# MINI_SAM_D51_007.net
KiCad netlist of a schematic drawn in EAGLE
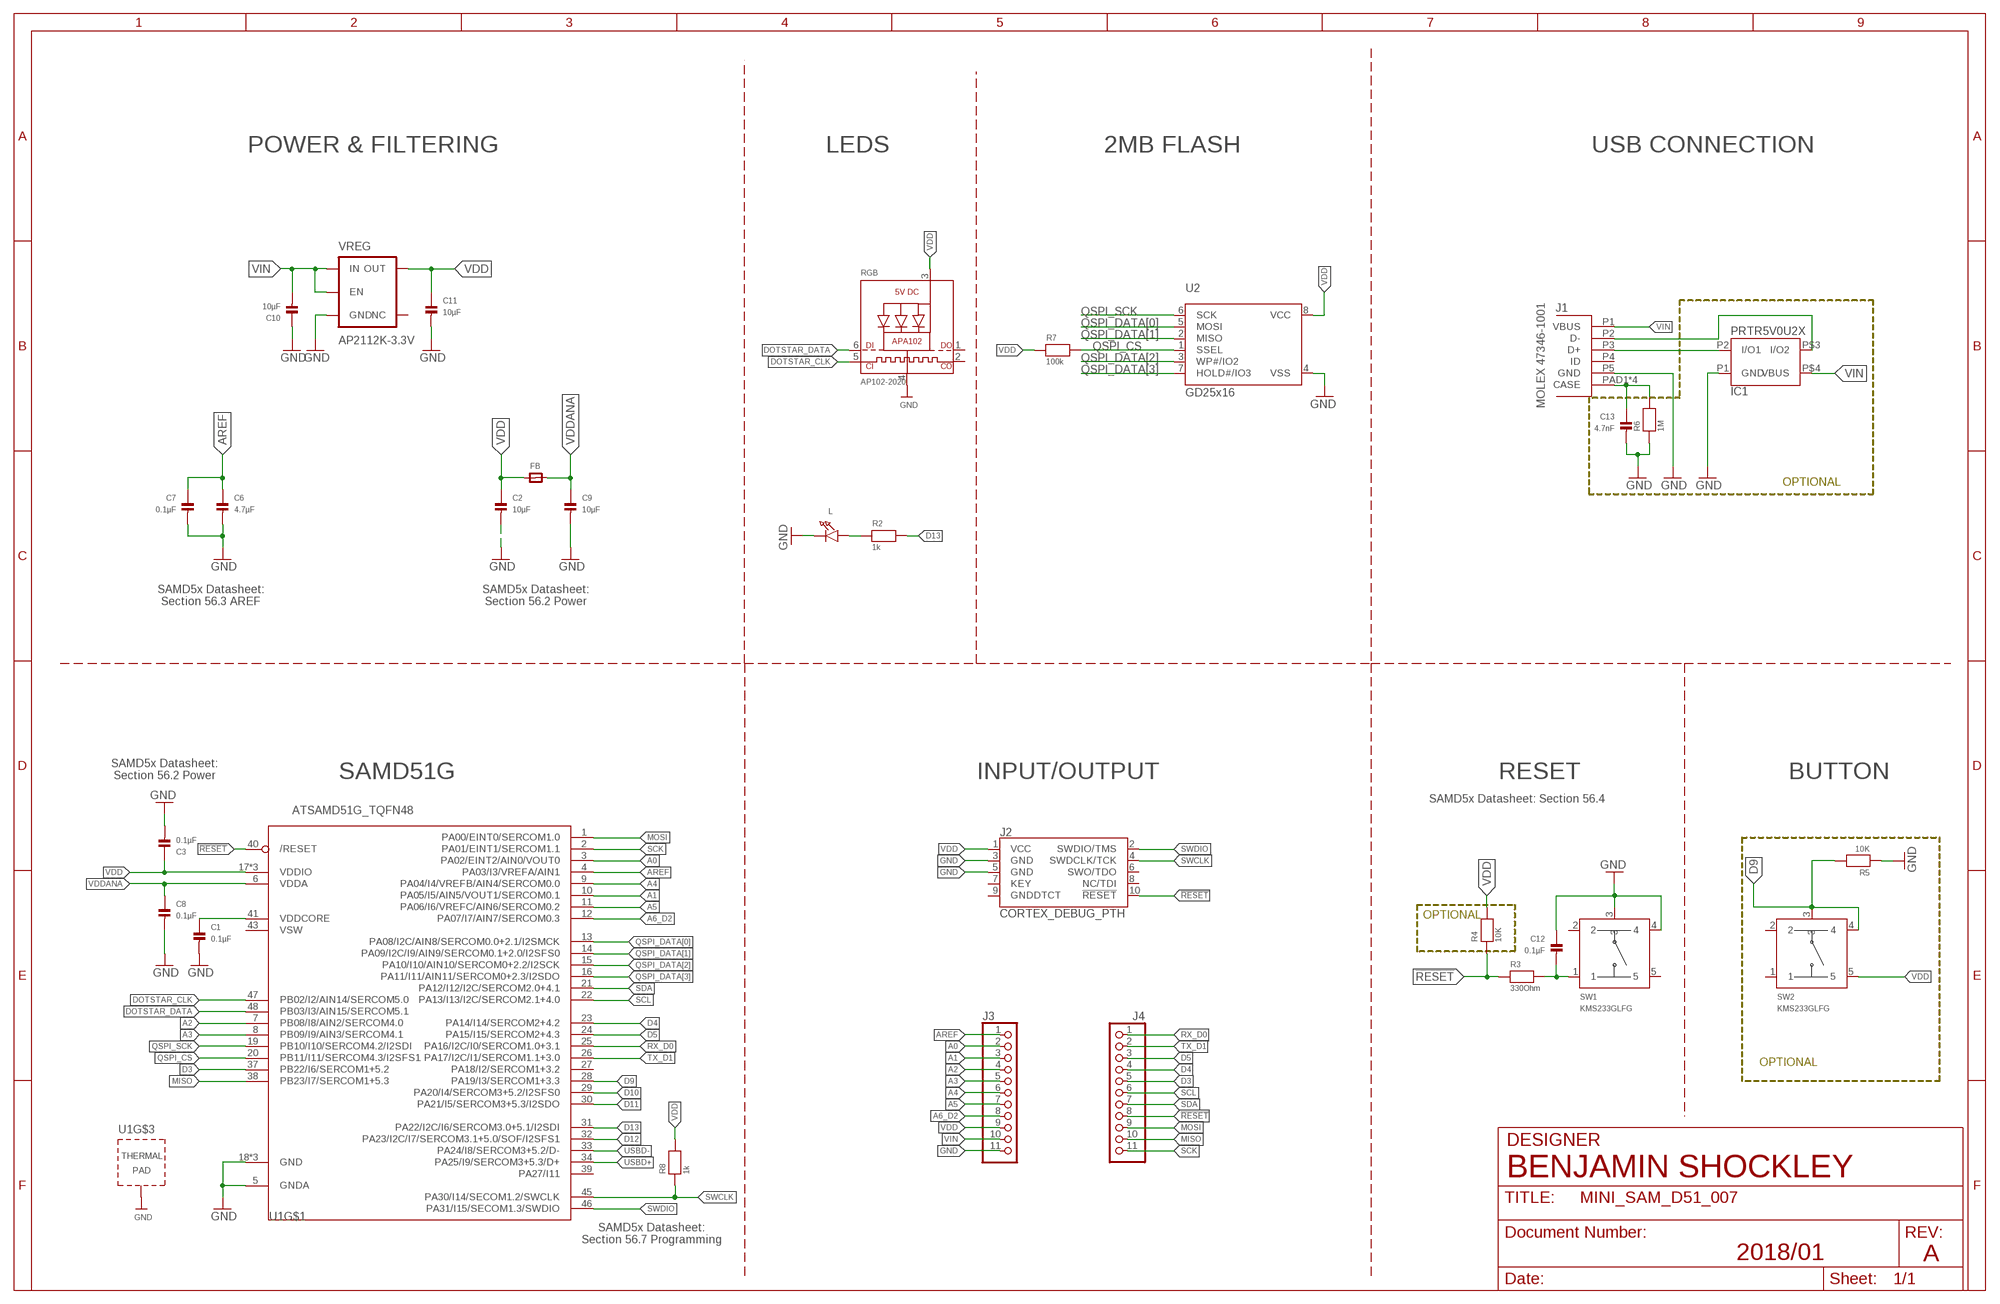
[diagram p0: schematic, sheet 1]

(export (version "E")
  (design (tool "Eeschema 10.0.6"))
  (components
    (comp (ref "C1")
      (value "0.1µF")
      (footprint "eagle-import:_0603MP")
      (libsource (lib "eagle-import") (part "CAP_CERAMIC_0603MP"))
    )
    (comp (ref "C2")
      (value "10µF")
      (footprint "eagle-import:_0603MP")
      (libsource (lib "eagle-import") (part "CAP_CERAMIC_0603MP"))
    )
    (comp (ref "C3")
      (value "0.1µF")
      (footprint "eagle-import:_0603MP")
      (libsource (lib "eagle-import") (part "CAP_CERAMIC_0603MP"))
    )
    (comp (ref "C6")
      (value "4.7µF")
      (footprint "eagle-import:_0603MP")
      (libsource (lib "eagle-import") (part "CAP_CERAMIC_0603MP"))
    )
    (comp (ref "C7")
      (value "0.1µF")
      (footprint "eagle-import:_0603MP")
      (libsource (lib "eagle-import") (part "CAP_CERAMIC_0603MP"))
    )
    (comp (ref "C8")
      (value "0.1µF")
      (footprint "eagle-import:_0603MP")
      (libsource (lib "eagle-import") (part "CAP_CERAMIC_0603MP"))
    )
    (comp (ref "C9")
      (value "10µF")
      (footprint "eagle-import:_0603MP")
      (libsource (lib "eagle-import") (part "CAP_CERAMIC_0603MP"))
    )
    (comp (ref "C10")
      (value "10µF")
      (footprint "eagle-import:_0603MP")
      (libsource (lib "eagle-import") (part "CAP_CERAMIC_0603MP"))
    )
    (comp (ref "C11")
      (value "10µF")
      (footprint "eagle-import:_0603MP")
      (libsource (lib "eagle-import") (part "CAP_CERAMIC_0603MP"))
    )
    (comp (ref "C12")
      (value "0.1µF")
      (footprint "eagle-import:_0603MP")
      (libsource (lib "eagle-import") (part "CAP_CERAMIC_0603MP"))
    )
    (comp (ref "C13")
      (value "4.7nF")
      (footprint "eagle-import:_0603MP")
      (libsource (lib "eagle-import") (part "CAP_CERAMIC_0603MP"))
    )
    (comp (ref "FB")
      (value "FERRITE_0603MP")
      (footprint "eagle-import:_0603MP")
      (libsource (lib "eagle-import") (part "FERRITE_0603MP"))
    )
    (comp (ref "IC1")
      (value "PRTR5V0U2X")
      (footprint "eagle-import:SOT143B_REFLOW")
      (libsource (lib "eagle-import") (part "PRTR5V0U2X"))
    )
    (comp (ref "J1")
      (value "MOLEX_47346-100147346")
      (footprint "eagle-import:MOLEX_47346-1001")
      (libsource (lib "eagle-import") (part "MOLEX_47346-100147346"))
    )
    (comp (ref "J2")
      (value "CORTEX_DEBUG_PTH")
      (footprint "eagle-import:2X5-PTH-1.27MM")
      (libsource (lib "eagle-import") (part "CORTEX_DEBUG_PTH"))
    )
    (comp (ref "J3")
      (value "PINHD-1X111X11_SMT")
      (footprint "eagle-import:1X11_SMT")
      (libsource (lib "eagle-import") (part "PINHD-1X111X11_SMT"))
    )
    (comp (ref "J4")
      (value "PINHD-1X111X11_SMT")
      (footprint "eagle-import:1X11_SMT")
      (libsource (lib "eagle-import") (part "PINHD-1X111X11_SMT"))
    )
    (comp (ref "L")
      (value "LED0603_NOOUTLINE")
      (footprint "eagle-import:CHIPLED_0603_NOOUTLINE")
      (libsource (lib "eagle-import") (part "LED0603_NOOUTLINE"))
    )
    (comp (ref "R2")
      (value "1k")
      (footprint "eagle-import:_0603MP")
      (libsource (lib "eagle-import") (part "RESISTOR_0603MP"))
    )
    (comp (ref "R3")
      (value "330Ohm")
      (footprint "eagle-import:_0603MP")
      (libsource (lib "eagle-import") (part "RESISTOR_0603MP"))
    )
    (comp (ref "R4")
      (value "10K")
      (footprint "eagle-import:_0603MP")
      (libsource (lib "eagle-import") (part "RESISTOR_0603MP"))
    )
    (comp (ref "R5")
      (value "10K")
      (footprint "eagle-import:_0603MP")
      (libsource (lib "eagle-import") (part "RESISTOR_0603MP"))
    )
    (comp (ref "R6")
      (value "1M")
      (footprint "eagle-import:_0603MP")
      (libsource (lib "eagle-import") (part "RESISTOR_0603MP"))
    )
    (comp (ref "R7")
      (value "100k")
      (footprint "eagle-import:_0603MP")
      (libsource (lib "eagle-import") (part "RESISTOR_0603MP"))
    )
    (comp (ref "R8")
      (value "1k")
      (footprint "eagle-import:_0603MP")
      (libsource (lib "eagle-import") (part "RESISTOR_0603MP"))
    )
    (comp (ref "RGB")
      (value "AP102-2020")
      (footprint "eagle-import:APA102_2020")
      (libsource (lib "eagle-import") (part "APA1022020"))
    )
    (comp (ref "SW1")
      (value "KMS233GLFG")
      (footprint "eagle-import:KMS_SWITCH")
      (libsource (lib "eagle-import") (part "KMS_SWITCHKMS"))
    )
    (comp (ref "SW2")
      (value "KMS233GLFG")
      (footprint "eagle-import:KMS_SWITCH")
      (libsource (lib "eagle-import") (part "KMS_SWITCHKMS"))
    )
    (comp (ref "U1")
      (value "ATSAMD51G_TQFN48")
      (footprint "eagle-import:TQFN48_7MM")
      (libsource (lib "eagle-import") (part "ATSAMD51G_TQFN48"))
    )
    (comp (ref "U2")
      (value "GD25x16")
      (footprint "eagle-import:USON8")
      (libsource (lib "eagle-import") (part "SPIFLASH_8PINUX"))
    )
    (comp (ref "VREG")
      (value "AP2112K-3.3V")
      (footprint "eagle-import:SOT23-5")
      (libsource (lib "eagle-import") (part "V_REG_AP2112K-3.3V"))
    )
  )
  (nets
    (net (code "1") (name "/VSW") (class "Default")
      (node (ref "U1") (pin "43") (pinfunction "VSW_43") (pintype "power_in"))
    )
    (net (code "2") (name "/~{RESET}") (class "Default")
      (node (ref "J2") (pin "10") (pinfunction "~{RESET}_10") (pintype "bidirectional"))
      (node (ref "J4") (pin "8") (pinfunction "8_8") (pintype "passive"))
      (node (ref "R3") (pin "1") (pinfunction "1_1") (pintype "passive"))
      (node (ref "R4") (pin "1") (pinfunction "1_1") (pintype "passive"))
      (node (ref "U1") (pin "40") (pinfunction "/RESET_40") (pintype "bidirectional"))
    )
    (net (code "3") (name "A0") (class "Default")
      (node (ref "J3") (pin "2") (pinfunction "2_2") (pintype "passive"))
      (node (ref "U1") (pin "3") (pinfunction "PA02/EINT2/AIN0/VOUT0_3") (pintype "bidirectional"))
    )
    (net (code "4") (name "A1") (class "Default")
      (node (ref "J3") (pin "3") (pinfunction "3_3") (pintype "passive"))
      (node (ref "U1") (pin "10") (pinfunction "PA05/I5/AIN5/VOUT1/SERCOM0.1_10") (pintype "bidirectional"))
    )
    (net (code "5") (name "A2") (class "Default")
      (node (ref "J3") (pin "4") (pinfunction "4_4") (pintype "passive"))
      (node (ref "U1") (pin "7") (pinfunction "PB08/I8/AIN2/SERCOM4.0_7") (pintype "bidirectional"))
    )
    (net (code "6") (name "A3") (class "Default")
      (node (ref "J3") (pin "5") (pinfunction "5_5") (pintype "passive"))
      (node (ref "U1") (pin "8") (pinfunction "PB09/I9/AIN3/SERCOM4.1_8") (pintype "bidirectional"))
    )
    (net (code "7") (name "A4") (class "Default")
      (node (ref "J3") (pin "6") (pinfunction "6_6") (pintype "passive"))
      (node (ref "U1") (pin "9") (pinfunction "PA04/I4/VREFB/AIN4/SERCOM0.0_9") (pintype "bidirectional"))
    )
    (net (code "8") (name "A5") (class "Default")
      (node (ref "J3") (pin "7") (pinfunction "7_7") (pintype "passive"))
      (node (ref "U1") (pin "11") (pinfunction "PA06/I6/VREFC/AIN6/SERCOM0.2_11") (pintype "bidirectional"))
    )
    (net (code "9") (name "A6_D2") (class "Default")
      (node (ref "J3") (pin "8") (pinfunction "8_8") (pintype "passive"))
      (node (ref "U1") (pin "12") (pinfunction "PA07/I7/AIN7/SERCOM0.3_12") (pintype "bidirectional"))
    )
    (net (code "10") (name "AREF") (class "Default")
      (node (ref "C6") (pin "1") (pinfunction "P$1_1") (pintype "passive"))
      (node (ref "C7") (pin "1") (pinfunction "P$1_1") (pintype "passive"))
      (node (ref "J3") (pin "1") (pinfunction "1_1") (pintype "passive"))
      (node (ref "U1") (pin "4") (pinfunction "PA03/I3/VREFA/AIN1_4") (pintype "bidirectional"))
    )
    (net (code "11") (name "D3") (class "Default")
      (node (ref "J4") (pin "5") (pinfunction "5_5") (pintype "passive"))
      (node (ref "U1") (pin "37") (pinfunction "PB22/I6/SERCOM1+5.2_37") (pintype "bidirectional"))
    )
    (net (code "12") (name "D4") (class "Default")
      (node (ref "J4") (pin "4") (pinfunction "4_4") (pintype "passive"))
      (node (ref "U1") (pin "23") (pinfunction "PA14/I14/SERCOM2+4.2_23") (pintype "bidirectional"))
    )
    (net (code "13") (name "D5") (class "Default")
      (node (ref "J4") (pin "3") (pinfunction "3_3") (pintype "passive"))
      (node (ref "U1") (pin "24") (pinfunction "PA15/I15/SERCOM2+4.3_24") (pintype "bidirectional"))
    )
    (net (code "14") (name "D9") (class "Default")
      (node (ref "R5") (pin "2") (pinfunction "2_2") (pintype "passive"))
      (node (ref "SW2") (pin "3") (pinfunction "3_3") (pintype "bidirectional"))
      (node (ref "SW2") (pin "4") (pinfunction "4_4") (pintype "bidirectional"))
      (node (ref "U1") (pin "28") (pinfunction "PA19/I3/SERCOM1+3.3_28") (pintype "bidirectional"))
    )
    (net (code "15") (name "D10") (class "Default")
      (node (ref "U1") (pin "29") (pinfunction "PA20/I4/SERCOM3+5.2/I2SFS0_29") (pintype "bidirectional"))
    )
    (net (code "16") (name "D11") (class "Default")
      (node (ref "U1") (pin "30") (pinfunction "PA21/I5/SERCOM3+5.3/I2SDO_30") (pintype "bidirectional"))
    )
    (net (code "17") (name "D12") (class "Default")
      (node (ref "U1") (pin "32") (pinfunction "PA23/I2C/I7/SERCOM3.1+5.0/SOF/I2SFS1_32") (pintype "bidirectional"))
    )
    (net (code "18") (name "D13") (class "Default")
      (node (ref "R2") (pin "2") (pinfunction "2_2") (pintype "passive"))
      (node (ref "U1") (pin "31") (pinfunction "PA22/I2C/I6/SERCOM3.0+5.1/I2SDI_31") (pintype "bidirectional"))
    )
    (net (code "19") (name "DOTSTAR_CLK") (class "Default")
      (node (ref "RGB") (pin "5") (pinfunction "CKI_5") (pintype "input"))
      (node (ref "U1") (pin "47") (pinfunction "PB02/I2/AIN14/SERCOM5.0_47") (pintype "bidirectional"))
    )
    (net (code "20") (name "DOTSTAR_DATA") (class "Default")
      (node (ref "RGB") (pin "6") (pinfunction "DI_6") (pintype "input"))
      (node (ref "U1") (pin "48") (pinfunction "PB03/I3/AIN15/SERCOM5.1_48") (pintype "bidirectional"))
    )
    (net (code "21") (name "GND") (class "Default")
      (node (ref "C1") (pin "2") (pinfunction "P$2_2") (pintype "passive"))
      (node (ref "C10") (pin "1") (pinfunction "P$1_1") (pintype "passive"))
      (node (ref "C11") (pin "2") (pinfunction "P$2_2") (pintype "passive"))
      (node (ref "C12") (pin "1") (pinfunction "P$1_1") (pintype "passive"))
      (node (ref "C13") (pin "2") (pinfunction "P$2_2") (pintype "passive"))
      (node (ref "C2") (pin "2") (pinfunction "P$2_2") (pintype "passive"))
      (node (ref "C3") (pin "2") (pinfunction "P$2_2") (pintype "passive"))
      (node (ref "C6") (pin "2") (pinfunction "P$2_2") (pintype "passive"))
      (node (ref "C7") (pin "2") (pinfunction "P$2_2") (pintype "passive"))
      (node (ref "C8") (pin "2") (pinfunction "P$2_2") (pintype "passive"))
      (node (ref "C9") (pin "2") (pinfunction "P$2_2") (pintype "passive"))
      (node (ref "IC1") (pin "P1") (pinfunction "GND_P1") (pintype "bidirectional"))
      (node (ref "J1") (pin "P5") (pinfunction "GND_P5") (pintype "power_in"))
      (node (ref "J2") (pin "3") (pinfunction "GND_3") (pintype "bidirectional"))
      (node (ref "J2") (pin "5") (pinfunction "GND_5") (pintype "bidirectional"))
      (node (ref "J3") (pin "11") (pinfunction "11_11") (pintype "passive"))
      (node (ref "L") (pin "C") (pinfunction "C_C") (pintype "passive"))
      (node (ref "R5") (pin "1") (pinfunction "1_1") (pintype "passive"))
      (node (ref "R6") (pin "1") (pinfunction "1_1") (pintype "passive"))
      (node (ref "RGB") (pin "4") (pinfunction "GND_4") (pintype "power_in"))
      (node (ref "SW1") (pin "3") (pinfunction "3_3") (pintype "bidirectional"))
      (node (ref "SW1") (pin "4") (pinfunction "4_4") (pintype "bidirectional"))
      (node (ref "U1") (pin "18") (pinfunction "GND_18") (pintype "power_in"))
      (node (ref "U1") (pin "35") (pinfunction "GND_35") (pintype "power_in"))
      (node (ref "U1") (pin "42") (pinfunction "GND_42") (pintype "power_in"))
      (node (ref "U1") (pin "5") (pinfunction "GNDA_5") (pintype "power_in"))
      (node (ref "U1") (pin "THERMAL") (pinfunction "TP_THERMAL") (pintype "power_in"))
      (node (ref "U2") (pin "4") (pinfunction "VSS_4") (pintype "bidirectional"))
      (node (ref "VREG") (pin "2") (pinfunction "GND_2") (pintype "input"))
    )
    (net (code "22") (name "MISO") (class "Default")
      (node (ref "J4") (pin "10") (pinfunction "10_10") (pintype "passive"))
      (node (ref "U1") (pin "38") (pinfunction "PB23/I7/SERCOM1+5.3_38") (pintype "bidirectional"))
    )
    (net (code "23") (name "MOSI") (class "Default")
      (node (ref "J4") (pin "9") (pinfunction "9_9") (pintype "passive"))
      (node (ref "U1") (pin "1") (pinfunction "PA00/EINT0/SERCOM1.0_1") (pintype "bidirectional"))
    )
    (net (code "24") (name "Net-(C1-P$1)") (class "Default")
      (node (ref "C1") (pin "1") (pinfunction "P$1_1") (pintype "passive"))
      (node (ref "U1") (pin "41") (pinfunction "VDDCORE_41") (pintype "power_in"))
    )
    (net (code "25") (name "Net-(C12-P$2)") (class "Default")
      (node (ref "C12") (pin "2") (pinfunction "P$2_2") (pintype "passive"))
      (node (ref "R3") (pin "2") (pinfunction "2_2") (pintype "passive"))
      (node (ref "SW1") (pin "1") (pinfunction "1_1") (pintype "bidirectional"))
    )
    (net (code "26") (name "Net-(C13-P$1)") (class "Default")
      (node (ref "C13") (pin "1") (pinfunction "P$1_1") (pintype "passive"))
      (node (ref "J1") (pin "PAD1") (pinfunction "CASE_PAD1") (pintype "bidirectional"))
      (node (ref "J1") (pin "PAD2") (pinfunction "CASE_PAD2") (pintype "bidirectional"))
      (node (ref "J1") (pin "PAD3") (pinfunction "CASE_PAD3") (pintype "bidirectional"))
      (node (ref "J1") (pin "PAD4") (pinfunction "CASE_PAD4") (pintype "bidirectional"))
      (node (ref "R6") (pin "2") (pinfunction "2_2") (pintype "passive"))
    )
    (net (code "27") (name "Net-(L-PadA)") (class "Default")
      (node (ref "L") (pin "A") (pinfunction "A_A") (pintype "passive"))
      (node (ref "R2") (pin "1") (pinfunction "1_1") (pintype "passive"))
    )
    (net (code "28") (name "QSPI_CS") (class "Default")
      (node (ref "R7") (pin "2") (pinfunction "2_2") (pintype "passive"))
      (node (ref "U1") (pin "20") (pinfunction "PB11/I11/SERCOM4.3/I2SFS1_20") (pintype "bidirectional"))
      (node (ref "U2") (pin "1") (pinfunction "SSEL_1") (pintype "bidirectional"))
    )
    (net (code "29") (name "QSPI_DATA[0]") (class "Default")
      (node (ref "U1") (pin "13") (pinfunction "PA08/I2C/AIN8/SERCOM0.0+2.1/I2SMCK_13") (pintype "bidirectional"))
      (node (ref "U2") (pin "5") (pinfunction "MOSI_5") (pintype "bidirectional"))
    )
    (net (code "30") (name "QSPI_DATA[1]") (class "Default")
      (node (ref "U1") (pin "14") (pinfunction "PA09/I2C/I9/AIN9/SERCOM0.1+2.0/I2SFS0_14") (pintype "bidirectional"))
      (node (ref "U2") (pin "2") (pinfunction "MISO_2") (pintype "bidirectional"))
    )
    (net (code "31") (name "QSPI_DATA[2]") (class "Default")
      (node (ref "U1") (pin "15") (pinfunction "PA10/I10/AIN10/SERCOM0+2.2/I2SCK_15") (pintype "bidirectional"))
      (node (ref "U2") (pin "3") (pinfunction "WP#/IO2_3") (pintype "bidirectional"))
    )
    (net (code "32") (name "QSPI_DATA[3]") (class "Default")
      (node (ref "U1") (pin "16") (pinfunction "PA11/I11/AIN11/SERCOM0+2.3/I2SDO_16") (pintype "bidirectional"))
      (node (ref "U2") (pin "7") (pinfunction "HOLD#/IO3_7") (pintype "bidirectional"))
    )
    (net (code "33") (name "QSPI_SCK") (class "Default")
      (node (ref "U1") (pin "19") (pinfunction "PB10/I10/SERCOM4.2/I2SDI_19") (pintype "bidirectional"))
      (node (ref "U2") (pin "6") (pinfunction "SCK_6") (pintype "bidirectional"))
    )
    (net (code "34") (name "RX_D0") (class "Default")
      (node (ref "J4") (pin "1") (pinfunction "1_1") (pintype "passive"))
      (node (ref "U1") (pin "25") (pinfunction "PA16/I2C/I0/SERCOM1.0+3.1_25") (pintype "bidirectional"))
    )
    (net (code "35") (name "SCK") (class "Default")
      (node (ref "J4") (pin "11") (pinfunction "11_11") (pintype "passive"))
      (node (ref "U1") (pin "2") (pinfunction "PA01/EINT1/SERCOM1.1_2") (pintype "bidirectional"))
    )
    (net (code "36") (name "SCL") (class "Default")
      (node (ref "J4") (pin "6") (pinfunction "6_6") (pintype "passive"))
      (node (ref "U1") (pin "22") (pinfunction "PA13/I13/I2C/SERCOM2.1+4.0_22") (pintype "bidirectional"))
    )
    (net (code "37") (name "SDA") (class "Default")
      (node (ref "J4") (pin "7") (pinfunction "7_7") (pintype "passive"))
      (node (ref "U1") (pin "21") (pinfunction "PA12/I12/I2C/SERCOM2.0+4.1_21") (pintype "bidirectional"))
    )
    (net (code "38") (name "SWCLK") (class "Default")
      (node (ref "J2") (pin "4") (pinfunction "SWDCLK/TCK_4") (pintype "bidirectional"))
      (node (ref "R8") (pin "1") (pinfunction "1_1") (pintype "passive"))
      (node (ref "U1") (pin "45") (pinfunction "PA30/I14/SECOM1.2/SWCLK_45") (pintype "bidirectional"))
    )
    (net (code "39") (name "SWDIO") (class "Default")
      (node (ref "J2") (pin "2") (pinfunction "SWDIO/TMS_2") (pintype "bidirectional"))
      (node (ref "U1") (pin "46") (pinfunction "PA31/I15/SECOM1.3/SWDIO_46") (pintype "bidirectional"))
    )
    (net (code "40") (name "TX_D1") (class "Default")
      (node (ref "J4") (pin "2") (pinfunction "2_2") (pintype "passive"))
      (node (ref "U1") (pin "26") (pinfunction "PA17/I2C/I1/SERCOM1.1+3.0_26") (pintype "bidirectional"))
    )
    (net (code "41") (name "USBD+") (class "Default")
      (node (ref "IC1") (pin "P2") (pinfunction "I/O1_P2") (pintype "bidirectional"))
      (node (ref "J1") (pin "P3") (pinfunction "D+_P3") (pintype "bidirectional"))
      (node (ref "U1") (pin "34") (pinfunction "PA25/I9/SERCOM3+5.3/D+_34") (pintype "bidirectional"))
    )
    (net (code "42") (name "USBD-") (class "Default")
      (node (ref "IC1") (pin "P$3") (pinfunction "I/O2_P$3") (pintype "bidirectional"))
      (node (ref "J1") (pin "P2") (pinfunction "D-_P2") (pintype "bidirectional"))
      (node (ref "U1") (pin "33") (pinfunction "PA24/I8/SERCOM3+5.2/D-_33") (pintype "bidirectional"))
    )
    (net (code "43") (name "VDD") (class "Default")
      (node (ref "C11") (pin "1") (pinfunction "P$1_1") (pintype "passive"))
      (node (ref "C2") (pin "1") (pinfunction "P$1_1") (pintype "passive"))
      (node (ref "C3") (pin "1") (pinfunction "P$1_1") (pintype "passive"))
      (node (ref "FB") (pin "1") (pinfunction "P$1_1") (pintype "passive"))
      (node (ref "J2") (pin "1") (pinfunction "VCC_1") (pintype "bidirectional"))
      (node (ref "J3") (pin "9") (pinfunction "9_9") (pintype "passive"))
      (node (ref "R4") (pin "2") (pinfunction "2_2") (pintype "passive"))
      (node (ref "R7") (pin "1") (pinfunction "1_1") (pintype "passive"))
      (node (ref "R8") (pin "2") (pinfunction "2_2") (pintype "passive"))
      (node (ref "RGB") (pin "3") (pinfunction "VDD_3") (pintype "power_in"))
      (node (ref "SW2") (pin "5") (pinfunction "5_5") (pintype "bidirectional"))
      (node (ref "U1") (pin "17") (pinfunction "VDDIO_17") (pintype "power_in"))
      (node (ref "U1") (pin "36") (pinfunction "VDDIO_36") (pintype "power_in"))
      (node (ref "U1") (pin "44") (pinfunction "VDDIO_44") (pintype "power_in"))
      (node (ref "U2") (pin "8") (pinfunction "VCC_8") (pintype "bidirectional"))
      (node (ref "VREG") (pin "5") (pinfunction "OUT_5") (pintype "passive"))
    )
    (net (code "44") (name "VDDANA") (class "Default")
      (node (ref "C8") (pin "1") (pinfunction "P$1_1") (pintype "passive"))
      (node (ref "C9") (pin "1") (pinfunction "P$1_1") (pintype "passive"))
      (node (ref "FB") (pin "2") (pinfunction "P$2_2") (pintype "passive"))
      (node (ref "U1") (pin "6") (pinfunction "VDDA_6") (pintype "power_in"))
    )
    (net (code "45") (name "VIN") (class "Default")
      (node (ref "C10") (pin "2") (pinfunction "P$2_2") (pintype "passive"))
      (node (ref "IC1") (pin "P$4") (pinfunction "VBUS_P$4") (pintype "bidirectional"))
      (node (ref "J1") (pin "P1") (pinfunction "VBUS_P1") (pintype "power_in"))
      (node (ref "J3") (pin "10") (pinfunction "10_10") (pintype "passive"))
      (node (ref "VREG") (pin "1") (pinfunction "IN_1") (pintype "input"))
      (node (ref "VREG") (pin "3") (pinfunction "EN_3") (pintype "input"))
    )
    (net (code "46") (name "unconnected-(J1-ID-PadP4)") (class "Default")
      (node (ref "J1") (pin "P4") (pinfunction "ID_P4") (pintype "bidirectional"))
    )
    (net (code "47") (name "unconnected-(J2-GNDDTCT-Pad9)") (class "Default")
      (node (ref "J2") (pin "9") (pinfunction "GNDDTCT_9") (pintype "bidirectional"))
    )
    (net (code "48") (name "unconnected-(J2-KEY-Pad7)") (class "Default")
      (node (ref "J2") (pin "7") (pinfunction "KEY_7") (pintype "bidirectional"))
    )
    (net (code "49") (name "unconnected-(J2-NC{slash}TDI-Pad8)") (class "Default")
      (node (ref "J2") (pin "8") (pinfunction "NC/TDI_8") (pintype "bidirectional"))
    )
    (net (code "50") (name "unconnected-(J2-SWO{slash}TDO-Pad6)") (class "Default")
      (node (ref "J2") (pin "6") (pinfunction "SWO/TDO_6") (pintype "bidirectional"))
    )
    (net (code "51") (name "unconnected-(RGB-CKO-Pad2)") (class "Default")
      (node (ref "RGB") (pin "2") (pinfunction "CKO_2") (pintype "output"))
    )
    (net (code "52") (name "unconnected-(RGB-DO-Pad1)") (class "Default")
      (node (ref "RGB") (pin "1") (pinfunction "DO_1") (pintype "output"))
    )
    (net (code "53") (name "unconnected-(SW1-Pad2)") (class "Default")
      (node (ref "SW1") (pin "2") (pinfunction "2_2") (pintype "bidirectional"))
    )
    (net (code "54") (name "unconnected-(SW1-Pad5)") (class "Default")
      (node (ref "SW1") (pin "5") (pinfunction "5_5") (pintype "bidirectional"))
    )
    (net (code "55") (name "unconnected-(SW2-Pad1)") (class "Default")
      (node (ref "SW2") (pin "1") (pinfunction "1_1") (pintype "bidirectional"))
    )
    (net (code "56") (name "unconnected-(SW2-Pad2)") (class "Default")
      (node (ref "SW2") (pin "2") (pinfunction "2_2") (pintype "bidirectional"))
    )
    (net (code "57") (name "unconnected-(U1A-PA18{slash}I2{slash}SERCOM1+3.2-Pad27)") (class "Default")
      (node (ref "U1") (pin "27") (pinfunction "PA18/I2/SERCOM1+3.2_27") (pintype "bidirectional"))
    )
    (net (code "58") (name "unconnected-(U1A-PA27{slash}I11-Pad39)") (class "Default")
      (node (ref "U1") (pin "39") (pinfunction "PA27/I11_39") (pintype "bidirectional"))
    )
    (net (code "59") (name "unconnected-(VREG-NC-Pad4)") (class "Default")
      (node (ref "VREG") (pin "4") (pinfunction "NC_4") (pintype "input"))
    )
  )
)
